# SX70_proto-flash-card.net
KiCad netlist of a schematic drawn in EAGLE
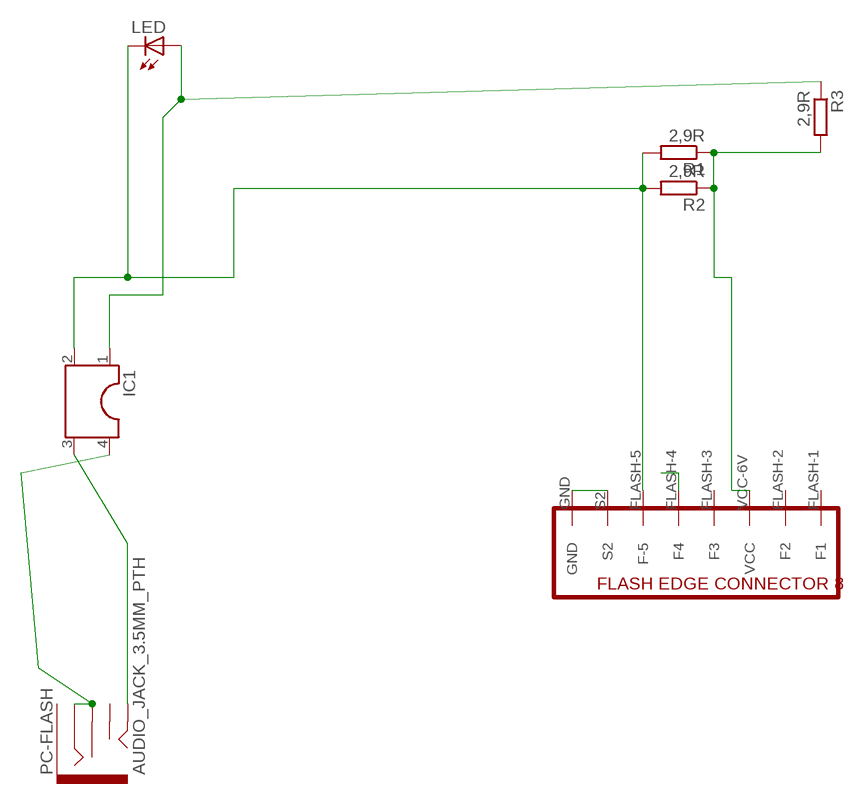
[diagram p0: schematic, sheet 1]

(export (version "E")
  (design (tool "Eeschema 10.0.6"))
  (components
    (comp (ref "FLASH-TESTER")
      (value "SX70-FLASH-EDGE8-MALE")
      (footprint "eagle-import:SX70-FLASH-EDGE8")
      (libsource (lib "eagle-import") (part "SX70-FLASH-EDGE8-MALE"))
    )
    (comp (ref "IC1")
      (value "DIL4")
      (footprint "eagle-import:DIL04")
      (libsource (lib "eagle-import") (part "DIL4"))
    )
    (comp (ref "LED")
      (value "LED3MM")
      (footprint "eagle-import:LED3MM")
      (libsource (lib "eagle-import") (part "LED3MM"))
    )
    (comp (ref "PC-FLASH")
      (value "AUDIO_JACK_3.5MM_PTH")
      (footprint "eagle-import:AUDIO-JACK")
      (libsource (lib "eagle-import") (part "AUDIO_JACK_3.5MM_PTH"))
    )
    (comp (ref "R1")
      (value "2,9R")
      (footprint "eagle-import:0204_7")
      (libsource (lib "eagle-import") (part "R-EU_0204/7"))
    )
    (comp (ref "R2")
      (value "2,9R")
      (footprint "eagle-import:0204_7")
      (libsource (lib "eagle-import") (part "R-EU_0204/7"))
    )
    (comp (ref "R3")
      (value "2,9R")
      (footprint "eagle-import:0204_7")
      (libsource (lib "eagle-import") (part "R-EU_0204/7"))
    )
  )
  (nets
    (net (code "1") (name "Net-(FLASH-TESTER-F-5)") (class "Default")
      (node (ref "FLASH-TESTER") (pin "FLASH-5") (pinfunction "F-5_FLASH-5") (pintype "bidirectional"))
      (node (ref "IC1") (pin "2") (pinfunction "2_2") (pintype "passive"))
      (node (ref "LED") (pin "K") (pinfunction "C_K") (pintype "passive"))
      (node (ref "R1") (pin "2") (pinfunction "2_2") (pintype "passive"))
      (node (ref "R2") (pin "2") (pinfunction "2_2") (pintype "passive"))
    )
    (net (code "2") (name "Net-(FLASH-TESTER-PadGND)") (class "Default")
      (node (ref "FLASH-TESTER") (pin "GND") (pinfunction "GND_GND") (pintype "bidirectional"))
      (node (ref "FLASH-TESTER") (pin "S2") (pinfunction "S2_S2") (pintype "bidirectional"))
    )
    (net (code "3") (name "Net-(FLASH-TESTER-VCC)") (class "Default")
      (node (ref "FLASH-TESTER") (pin "VCC-6V") (pinfunction "VCC_VCC-6V") (pintype "bidirectional"))
      (node (ref "R1") (pin "1") (pinfunction "1_1") (pintype "passive"))
      (node (ref "R2") (pin "1") (pinfunction "1_1") (pintype "passive"))
      (node (ref "R3") (pin "2") (pinfunction "2_2") (pintype "passive"))
    )
    (net (code "4") (name "Net-(IC1-Pad1)") (class "Default")
      (node (ref "IC1") (pin "1") (pinfunction "1_1") (pintype "passive"))
      (node (ref "LED") (pin "A") (pinfunction "A_A") (pintype "passive"))
      (node (ref "R3") (pin "1") (pinfunction "1_1") (pintype "passive"))
    )
    (net (code "5") (name "Net-(IC1-Pad3)") (class "Default")
      (node (ref "IC1") (pin "3") (pinfunction "3_3") (pintype "passive"))
      (node (ref "PC-FLASH") (pin "TIP") (pinfunction "TIP_TIP") (pintype "bidirectional"))
    )
    (net (code "6") (name "Net-(IC1-Pad4)") (class "Default")
      (node (ref "IC1") (pin "4") (pinfunction "4_4") (pintype "passive"))
      (node (ref "PC-FLASH") (pin "RING") (pinfunction "RING_RING") (pintype "bidirectional"))
      (node (ref "PC-FLASH") (pin "RSH") (pinfunction "RSH_RSH") (pintype "bidirectional"))
    )
    (net (code "7") (name "unconnected-(FLASH-TESTER-F1-PadFLASH-1)") (class "Default")
      (node (ref "FLASH-TESTER") (pin "FLASH-1") (pinfunction "F1_FLASH-1") (pintype "bidirectional"))
    )
    (net (code "8") (name "unconnected-(FLASH-TESTER-F2-PadFLASH-2)") (class "Default")
      (node (ref "FLASH-TESTER") (pin "FLASH-2") (pinfunction "F2_FLASH-2") (pintype "bidirectional"))
    )
    (net (code "9") (name "unconnected-(FLASH-TESTER-F3-PadFLASH-3)") (class "Default")
      (node (ref "FLASH-TESTER") (pin "FLASH-3") (pinfunction "F3_FLASH-3") (pintype "bidirectional"))
    )
    (net (code "10") (name "unconnected-(FLASH-TESTER-F4-PadFLASH-4)") (class "Default")
      (node (ref "FLASH-TESTER") (pin "FLASH-4") (pinfunction "F4_FLASH-4") (pintype "bidirectional"))
    )
    (net (code "11") (name "unconnected-(PC-FLASH-PadSLEEVE)") (class "Default")
      (node (ref "PC-FLASH") (pin "SLEEVE") (pinfunction "SLEEVE_SLEEVE") (pintype "bidirectional"))
    )
    (net (code "12") (name "unconnected-(PC-FLASH-PadTSH)") (class "Default")
      (node (ref "PC-FLASH") (pin "TSH") (pinfunction "TSH_TSH") (pintype "bidirectional"))
    )
  )
)
